# RS485.net
KiCad netlist of a schematic drawn in Altium Designer
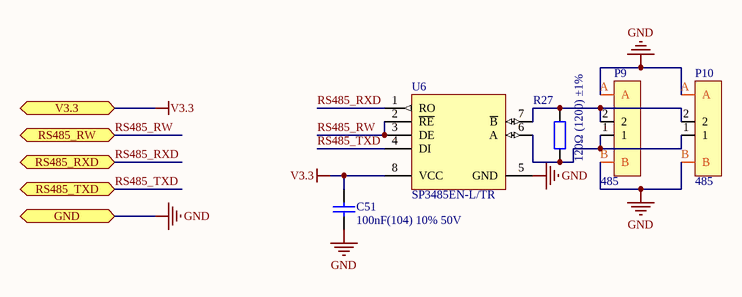
[diagram p0: RS485.SchDoc]

(export (version "E")
  (design (tool "Eeschema 10.0.6"))
  (components
    (comp (ref "C51")
      (value "100nF(104) 10% 50V")
      (footprint "0805_C")
      (description "贴片电容")
      (libsource (lib "Miscellaneous Devices LC") (part "0805 100nF(104) 10% 50V"))
    )
    (comp (ref "P9") (value "485") (footprint "2P_XH2.54_W") (libsource (lib "mylib") (part "2P_XH2.54_W")))
    (comp (ref "P10") (value "485") (footprint "2P_XH2.54_W") (libsource (lib "mylib") (part "2P_XH2.54_W")))
    (comp (ref "R27")
      (value "120Ω (1200) ±1%")
      (footprint "0805_R")
      (description "贴片电阻")
      (libsource (lib "Miscellaneous Devices LC") (part "0805 120Ω (1200) 1%"))
    )
    (comp (ref "U6")
      (value "SP3485EN-L/TR")
      (footprint "SOIC-8_150mil")
      (description "RS-485/RS-422")
      (libsource (lib "Miscellaneous Devices LC") (part "SP3485EN-L/TR_[C8963]"))
    )
  )
  (nets
    (net (code "1") (name "/RS485_RW") (class "Default")
      (node (ref "U6") (pin "2") (pinfunction "~{RE}_2") (pintype "passive"))
      (node (ref "U6") (pin "3") (pinfunction "DE_3") (pintype "passive"))
    )
    (net (code "2") (name "/RS485_RXD") (class "Default")
      (node (ref "U6") (pin "1") (pinfunction "RO_1") (pintype "output"))
    )
    (net (code "3") (name "/RS485_TXD") (class "Default")
      (node (ref "U6") (pin "4") (pinfunction "DI_4") (pintype "passive"))
    )
    (net (code "4") (name "GND") (class "Default")
      (node (ref "C51") (pin "1") (pinfunction "1_1") (pintype "passive"))
      (node (ref "P10") (pin "A") (pinfunction "A_A") (pintype "passive"))
      (node (ref "P10") (pin "B") (pinfunction "B_B") (pintype "passive"))
      (node (ref "P9") (pin "A") (pinfunction "A_A") (pintype "passive"))
      (node (ref "P9") (pin "B") (pinfunction "B_B") (pintype "passive"))
      (node (ref "U6") (pin "5") (pinfunction "GND_5") (pintype "power_in"))
    )
    (net (code "5") (name "Net-(U6-A)") (class "Default")
      (node (ref "P10") (pin "1") (pinfunction "1_1") (pintype "passive"))
      (node (ref "P9") (pin "1") (pinfunction "1_1") (pintype "passive"))
      (node (ref "R27") (pin "1") (pinfunction "1_1") (pintype "passive"))
      (node (ref "U6") (pin "6") (pinfunction "A_6") (pintype "bidirectional"))
    )
    (net (code "6") (name "Net-(U6-~{B})") (class "Default")
      (node (ref "P10") (pin "2") (pinfunction "2_2") (pintype "passive"))
      (node (ref "P9") (pin "2") (pinfunction "2_2") (pintype "passive"))
      (node (ref "R27") (pin "2") (pinfunction "2_2") (pintype "passive"))
      (node (ref "U6") (pin "7") (pinfunction "~{B}_7") (pintype "bidirectional"))
    )
    (net (code "7") (name "V3.3") (class "Default")
      (node (ref "C51") (pin "2") (pinfunction "2_2") (pintype "passive"))
      (node (ref "U6") (pin "8") (pinfunction "VCC_8") (pintype "power_in"))
    )
  )
)
